# AMI_601.net
KiCad netlist of a schematic drawn in EAGLE
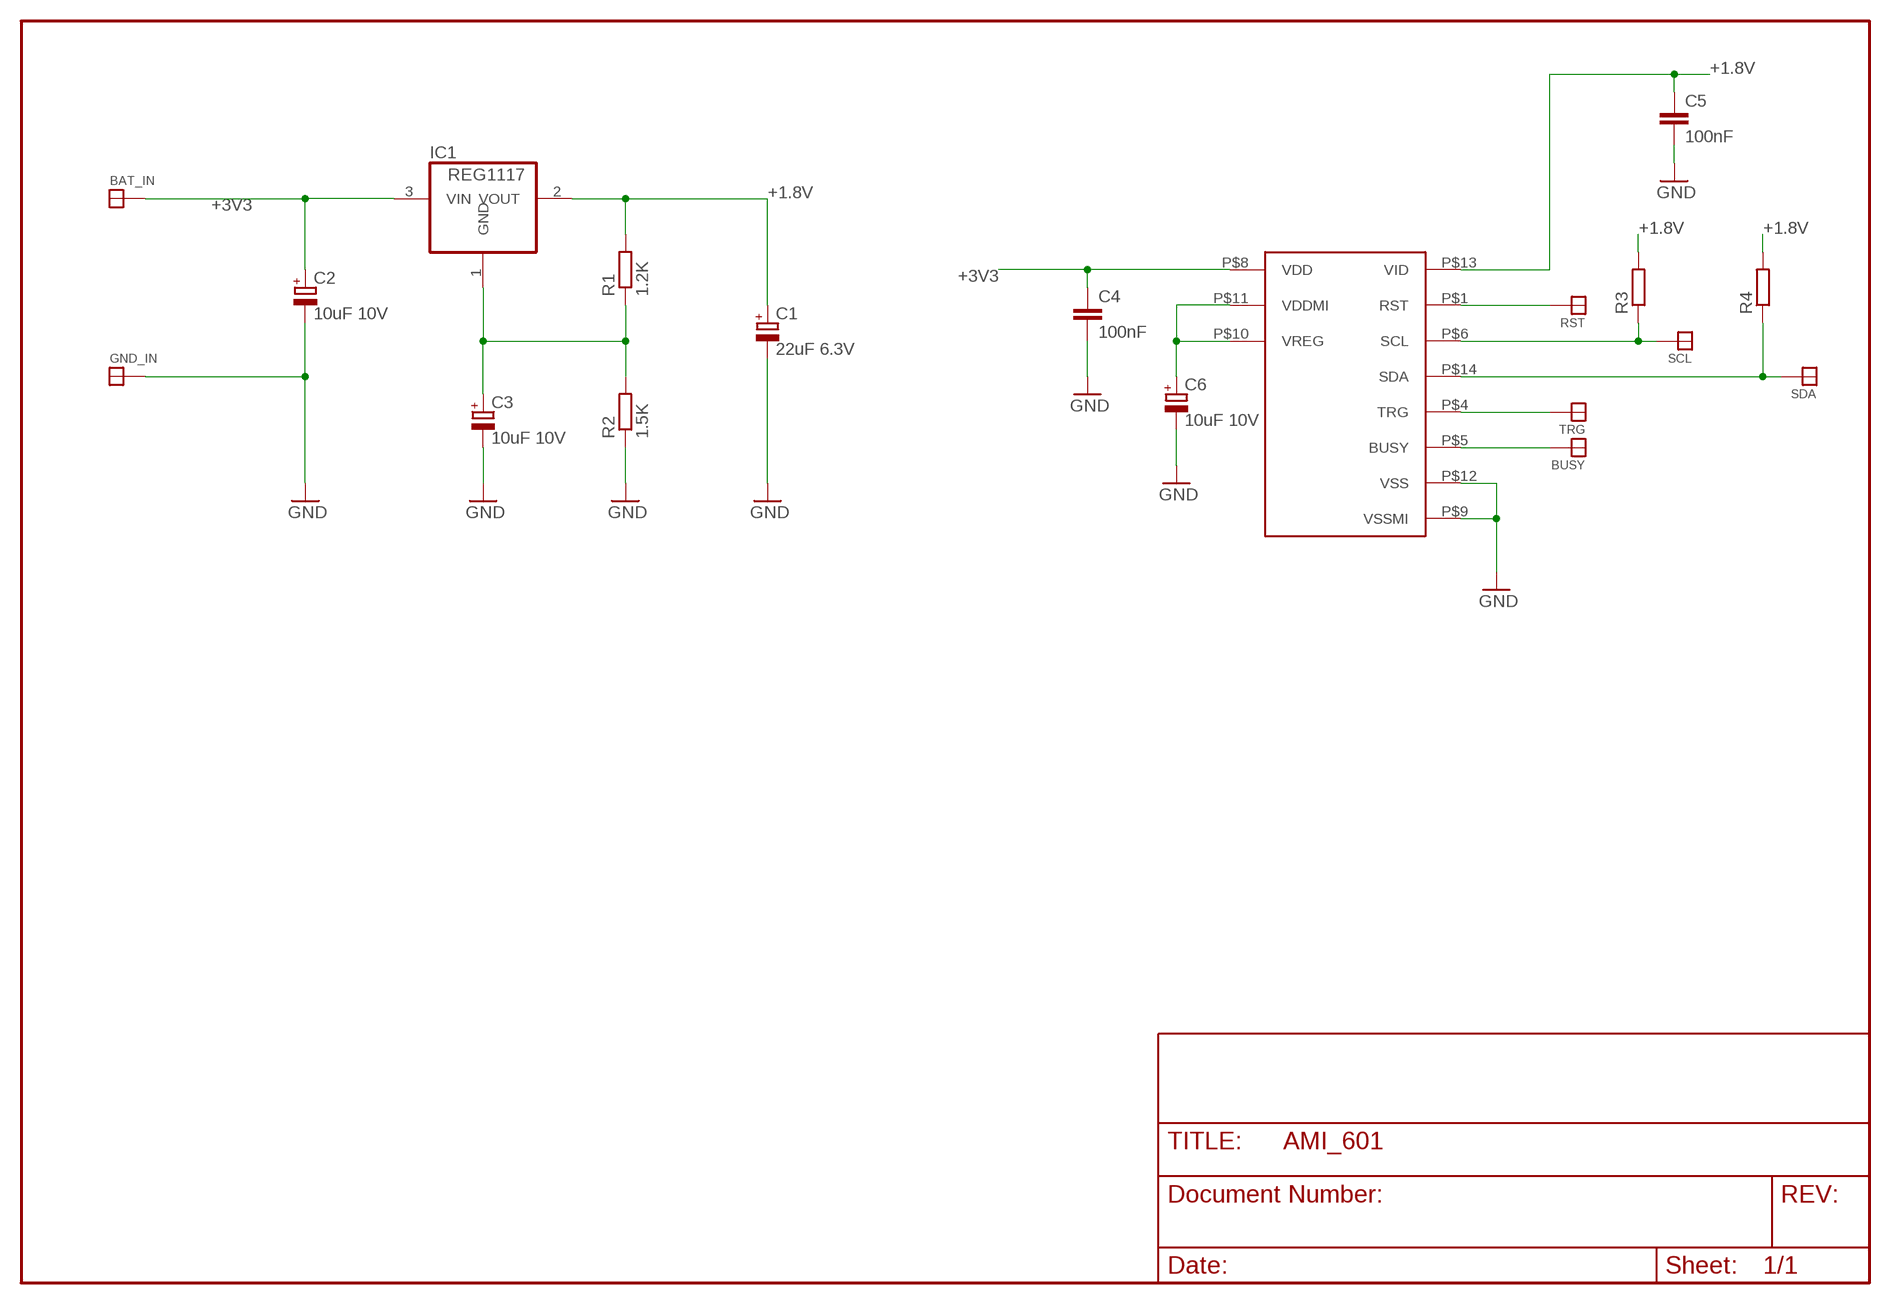
[diagram p0: schematic, sheet 1]

(export (version "E")
  (design (tool "Eeschema 10.0.6"))
  (components
    (comp (ref "BAT_IN")
      (value "SOLDER_PAD150_75")
      (footprint "eagle-import:SOLD_PAD_150_75")
      (libsource (lib "eagle-import") (part "SOLDER_PAD150_75"))
    )
    (comp (ref "BUSY")
      (value "SOLDER_PAD150_75")
      (footprint "eagle-import:SOLD_PAD_150_75")
      (libsource (lib "eagle-import") (part "SOLDER_PAD150_75"))
    )
    (comp (ref "C1")
      (value "22uF 6.3V")
      (footprint "eagle-import:CT3528")
      (libsource (lib "eagle-import") (part "CPOL-EUCT3528"))
    )
    (comp (ref "C2")
      (value "10uF 10V")
      (footprint "eagle-import:CT3216")
      (libsource (lib "eagle-import") (part "CPOL-EUCT3216"))
    )
    (comp (ref "C3")
      (value "10uF 10V")
      (footprint "eagle-import:CT3216")
      (libsource (lib "eagle-import") (part "CPOL-EUCT3216"))
    )
    (comp (ref "C4")
      (value "100nF")
      (footprint "eagle-import:C0805K")
      (libsource (lib "eagle-import") (part "C-EUC0805K"))
    )
    (comp (ref "C5")
      (value "100nF")
      (footprint "eagle-import:C0805K")
      (libsource (lib "eagle-import") (part "C-EUC0805K"))
    )
    (comp (ref "C6")
      (value "10uF 10V")
      (footprint "eagle-import:CT3216")
      (libsource (lib "eagle-import") (part "CPOL-EUCT3216"))
    )
    (comp (ref "GND_IN")
      (value "SOLDER_PAD150_75")
      (footprint "eagle-import:SOLD_PAD_150_75")
      (libsource (lib "eagle-import") (part "SOLDER_PAD150_75"))
    )
    (comp (ref "IC1")
      (value "REG1117")
      (footprint "eagle-import:SOT223")
      (libsource (lib "eagle-import") (part "REG1117"))
    )
    (comp (ref "R1")
      (value "1.2K")
      (footprint "eagle-import:M0805")
      (libsource (lib "eagle-import") (part "R-EU_M0805"))
    )
    (comp (ref "R2")
      (value "1.5K")
      (footprint "eagle-import:M0805")
      (libsource (lib "eagle-import") (part "R-EU_M0805"))
    )
    (comp (ref "R3")
      (value "R-EU_M0805")
      (footprint "eagle-import:M0805")
      (libsource (lib "eagle-import") (part "R-EU_M0805"))
    )
    (comp (ref "R4")
      (value "R-EU_M0805")
      (footprint "eagle-import:M0805")
      (libsource (lib "eagle-import") (part "R-EU_M0805"))
    )
    (comp (ref "RST")
      (value "SOLDER_PAD150_75")
      (footprint "eagle-import:SOLD_PAD_150_75")
      (libsource (lib "eagle-import") (part "SOLDER_PAD150_75"))
    )
    (comp (ref "SCL")
      (value "SOLDER_PAD150_75")
      (footprint "eagle-import:SOLD_PAD_150_75")
      (libsource (lib "eagle-import") (part "SOLDER_PAD150_75"))
    )
    (comp (ref "SDA")
      (value "SOLDER_PAD150_75")
      (footprint "eagle-import:SOLD_PAD_150_75")
      (libsource (lib "eagle-import") (part "SOLDER_PAD150_75"))
    )
    (comp (ref "TRG")
      (value "SOLDER_PAD150_75")
      (footprint "eagle-import:SOLD_PAD_150_75")
      (libsource (lib "eagle-import") (part "SOLDER_PAD150_75"))
    )
    (comp (ref "U$1")
      (value "AMI601")
      (footprint "eagle-import:AMI_601")
      (libsource (lib "eagle-import") (part "AMI601"))
    )
  )
  (nets
    (net (code "1") (name "/+1.8V") (class "Default")
      (node (ref "C1") (pin "+") (pinfunction "+_+") (pintype "passive"))
      (node (ref "C5") (pin "1") (pinfunction "1_1") (pintype "passive"))
      (node (ref "IC1") (pin "2") (pinfunction "VOUT_2") (pintype "output"))
      (node (ref "R1") (pin "2") (pinfunction "2_2") (pintype "passive"))
      (node (ref "R3") (pin "2") (pinfunction "2_2") (pintype "passive"))
      (node (ref "R4") (pin "2") (pinfunction "2_2") (pintype "passive"))
      (node (ref "U$1") (pin "P$13") (pinfunction "VID_P$13") (pintype "bidirectional"))
    )
    (net (code "2") (name "/+3V3") (class "Default")
      (node (ref "BAT_IN") (pin "P$1") (pinfunction "P$1_P$1") (pintype "bidirectional"))
      (node (ref "C2") (pin "+") (pinfunction "+_+") (pintype "passive"))
      (node (ref "C4") (pin "1") (pinfunction "1_1") (pintype "passive"))
      (node (ref "IC1") (pin "3") (pinfunction "VIN_3") (pintype "input"))
      (node (ref "U$1") (pin "P$8") (pinfunction "VDD_P$8") (pintype "bidirectional"))
    )
    (net (code "3") (name "GND") (class "Default")
      (node (ref "C1") (pin "-") (pinfunction "-_-") (pintype "passive"))
      (node (ref "C2") (pin "-") (pinfunction "-_-") (pintype "passive"))
      (node (ref "C3") (pin "-") (pinfunction "-_-") (pintype "passive"))
      (node (ref "C4") (pin "2") (pinfunction "2_2") (pintype "passive"))
      (node (ref "C5") (pin "2") (pinfunction "2_2") (pintype "passive"))
      (node (ref "C6") (pin "-") (pinfunction "-_-") (pintype "passive"))
      (node (ref "GND_IN") (pin "P$1") (pinfunction "P$1_P$1") (pintype "bidirectional"))
      (node (ref "R2") (pin "1") (pinfunction "1_1") (pintype "passive"))
      (node (ref "U$1") (pin "P$12") (pinfunction "VSS_P$12") (pintype "bidirectional"))
      (node (ref "U$1") (pin "P$9") (pinfunction "VSSMI_P$9") (pintype "bidirectional"))
    )
    (net (code "4") (name "Net-(IC1-GND)") (class "Default")
      (node (ref "C3") (pin "+") (pinfunction "+_+") (pintype "passive"))
      (node (ref "IC1") (pin "1") (pinfunction "GND_1") (pintype "power_in"))
      (node (ref "R1") (pin "1") (pinfunction "1_1") (pintype "passive"))
      (node (ref "R2") (pin "2") (pinfunction "2_2") (pintype "passive"))
    )
    (net (code "5") (name "Net-(U$1-BUSY)") (class "Default")
      (node (ref "BUSY") (pin "P$1") (pinfunction "P$1_P$1") (pintype "bidirectional"))
      (node (ref "U$1") (pin "P$5") (pinfunction "BUSY_P$5") (pintype "bidirectional"))
    )
    (net (code "6") (name "Net-(U$1-RST)") (class "Default")
      (node (ref "RST") (pin "P$1") (pinfunction "P$1_P$1") (pintype "bidirectional"))
      (node (ref "U$1") (pin "P$1") (pinfunction "RST_P$1") (pintype "bidirectional"))
    )
    (net (code "7") (name "Net-(U$1-SCL)") (class "Default")
      (node (ref "R3") (pin "1") (pinfunction "1_1") (pintype "passive"))
      (node (ref "SCL") (pin "P$1") (pinfunction "P$1_P$1") (pintype "bidirectional"))
      (node (ref "U$1") (pin "P$6") (pinfunction "SCL_P$6") (pintype "bidirectional"))
    )
    (net (code "8") (name "Net-(U$1-SDA)") (class "Default")
      (node (ref "R4") (pin "1") (pinfunction "1_1") (pintype "passive"))
      (node (ref "SDA") (pin "P$1") (pinfunction "P$1_P$1") (pintype "bidirectional"))
      (node (ref "U$1") (pin "P$14") (pinfunction "SDA_P$14") (pintype "bidirectional"))
    )
    (net (code "9") (name "Net-(U$1-TRG)") (class "Default")
      (node (ref "TRG") (pin "P$1") (pinfunction "P$1_P$1") (pintype "bidirectional"))
      (node (ref "U$1") (pin "P$4") (pinfunction "TRG_P$4") (pintype "bidirectional"))
    )
    (net (code "10") (name "Net-(U$1-VDDMI)") (class "Default")
      (node (ref "C6") (pin "+") (pinfunction "+_+") (pintype "passive"))
      (node (ref "U$1") (pin "P$10") (pinfunction "VREG_P$10") (pintype "bidirectional"))
      (node (ref "U$1") (pin "P$11") (pinfunction "VDDMI_P$11") (pintype "bidirectional"))
    )
  )
)
